# Power_supply.net
KiCad netlist of a schematic drawn in Altium Designer
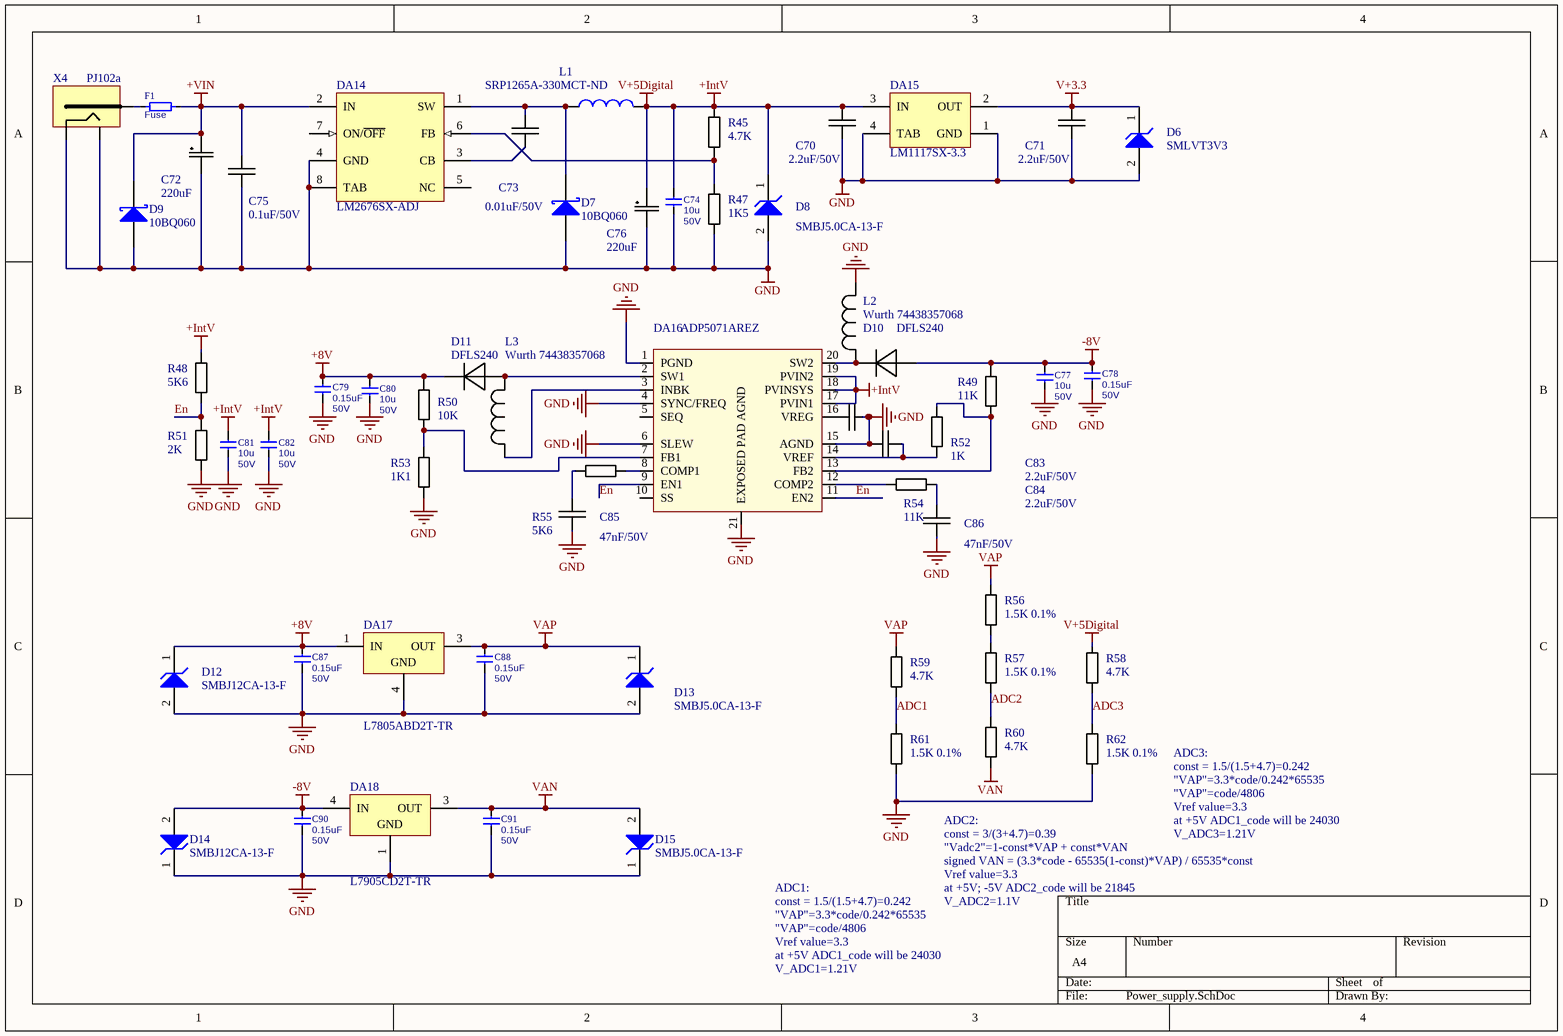
[diagram p0: Power_supply.SchDoc]

(export (version "E")
  (design (tool "Eeschema 10.0.6"))
  (components
    (comp (ref "C70")
      (value "2.2uF/50V")
      (footprint "CAPACITOR 0603")
      (fields (field (name "MANUFACTURER_PART_NUMBER") "C1608X7R1A225K080AC"))
      (libsource (lib "Maks_lib") (part "Capasitor"))
    )
    (comp (ref "C71")
      (value "2.2uF/50V")
      (footprint "CAPACITOR 0603")
      (fields (field (name "MANUFACTURER_PART_NUMBER") "C1608X7R1A225K080AC"))
      (libsource (lib "Maks_lib") (part "Capasitor"))
    )
    (comp (ref "C72")
      (value "220uF")
      (footprint "CapacitorG")
      (description "Конденсатор электролит бочонок 5мм, диаметр 13")
      (fields (field (name "MANUFACTURER_PART_NUMBER") "UWT1V221MNL1GS"))
      (libsource (lib "el") (part "CapPolBarrel"))
    )
    (comp (ref "C73")
      (value "0.01uF/50V")
      (footprint "CAPACITOR 0603")
      (fields (field (name "MANUFACTURER_PART_NUMBER") "CGA3E2X7R1H103K080AA"))
      (libsource (lib "Maks_lib") (part "Capasitor"))
    )
    (comp (ref "C74")
      (value "~")
      (footprint "Passive_components:C_1210")
      (description "Capacitor")
      (fields
        (field (name "CAPACITANCE") "10u")
        (field (name "VOLTAGE") "50V")
        (field (name "MANUFACTURER_PART_NUMBER") "CGA6P3X7S1H106M250AB")
      )
      (libsource (lib "Passive_components") (part "C_SMD_ceramic"))
    )
    (comp (ref "C75")
      (value "0.1uF/50V")
      (footprint "CAPACITOR 0603")
      (fields (field (name "MANUFACTURER_PART_NUMBER") "CGA3E2X7R1H104K080AA"))
      (libsource (lib "Maks_lib") (part "Capasitor"))
    )
    (comp (ref "C76")
      (value "220uF")
      (footprint "CapacitorG")
      (description "Конденсатор электролит бочонок 5мм, диаметр 13")
      (fields (field (name "MANUFACTURER_PART_NUMBER") "UWT1V221MNL1GS"))
      (libsource (lib "el") (part "CapPolBarrel"))
    )
    (comp (ref "C77")
      (value "~")
      (footprint "Passive_components:C_1210")
      (description "Capacitor")
      (fields
        (field (name "CAPACITANCE") "10u")
        (field (name "VOLTAGE") "50V")
        (field (name "MANUFACTURER_PART_NUMBER") "CGA6P3X7S1H106M250AB")
      )
      (libsource (lib "Passive_components") (part "C_SMD_ceramic"))
    )
    (comp (ref "C78")
      (value "~")
      (footprint "Passive_components:C_1206")
      (description "Capacitor")
      (fields
        (field (name "CAPACITANCE") "0.15uF")
        (field (name "VOLTAGE") "50V")
        (field (name "MANUFACTURER_PART_NUMBER") "ECP-U1C154MA5")
      )
      (libsource (lib "Passive_components") (part "C_SMD_ceramic"))
    )
    (comp (ref "C79")
      (value "~")
      (footprint "Passive_components:C_1206")
      (description "Capacitor")
      (fields
        (field (name "CAPACITANCE") "0.15uF")
        (field (name "VOLTAGE") "50V")
        (field (name "MANUFACTURER_PART_NUMBER") "ECP-U1C154MA5")
      )
      (libsource (lib "Passive_components") (part "C_SMD_ceramic"))
    )
    (comp (ref "C80")
      (value "~")
      (footprint "Passive_components:C_1210")
      (description "Capacitor")
      (fields
        (field (name "CAPACITANCE") "10u")
        (field (name "VOLTAGE") "50V")
        (field (name "MANUFACTURER_PART_NUMBER") "CGA6P3X7S1H106M250AB")
      )
      (libsource (lib "Passive_components") (part "C_SMD_ceramic"))
    )
    (comp (ref "C81")
      (value "~")
      (footprint "Passive_components:C_1210")
      (description "Capacitor")
      (fields
        (field (name "CAPACITANCE") "10u")
        (field (name "VOLTAGE") "50V")
        (field (name "MANUFACTURER_PART_NUMBER") "CGA6P3X7S1H106M250AB")
      )
      (libsource (lib "Passive_components") (part "C_SMD_ceramic"))
    )
    (comp (ref "C82")
      (value "~")
      (footprint "Passive_components:C_1210")
      (description "Capacitor")
      (fields
        (field (name "CAPACITANCE") "10u")
        (field (name "VOLTAGE") "50V")
        (field (name "MANUFACTURER_PART_NUMBER") "CGA6P3X7S1H106M250AB")
      )
      (libsource (lib "Passive_components") (part "C_SMD_ceramic"))
    )
    (comp (ref "C83")
      (value "2.2uF/50V")
      (footprint "CAPACITOR 0603")
      (fields (field (name "MANUFACTURER_PART_NUMBER") "C1608X7R1A225K080AC"))
      (libsource (lib "Maks_lib") (part "Capasitor"))
    )
    (comp (ref "C84")
      (value "2.2uF/50V")
      (footprint "CAPACITOR 0603")
      (fields (field (name "MANUFACTURER_PART_NUMBER") "C1608X7R1A225K080AC"))
      (libsource (lib "Maks_lib") (part "Capasitor"))
    )
    (comp (ref "C85")
      (value "47nF/50V")
      (footprint "CAPACITOR 0603")
      (fields (field (name "MANUFACTURER_PART_NUMBER") "C1608X8R1H473K080AA"))
      (libsource (lib "Maks_lib") (part "Capasitor"))
    )
    (comp (ref "C86")
      (value "47nF/50V")
      (footprint "CAPACITOR 0603")
      (fields (field (name "MANUFACTURER_PART_NUMBER") "C1608X8R1H473K080AA"))
      (libsource (lib "Maks_lib") (part "Capasitor"))
    )
    (comp (ref "C87")
      (value "~")
      (footprint "Passive_components:C_1206")
      (description "Capacitor")
      (fields
        (field (name "CAPACITANCE") "0.15uF")
        (field (name "VOLTAGE") "50V")
        (field (name "MANUFACTURER_PART_NUMBER") "ECP-U1C154MA5")
      )
      (libsource (lib "Passive_components") (part "C_SMD_ceramic"))
    )
    (comp (ref "C88")
      (value "~")
      (footprint "Passive_components:C_1206")
      (description "Capacitor")
      (fields
        (field (name "CAPACITANCE") "0.15uF")
        (field (name "VOLTAGE") "50V")
        (field (name "MANUFACTURER_PART_NUMBER") "ECP-U1C154MA5")
      )
      (libsource (lib "Passive_components") (part "C_SMD_ceramic"))
    )
    (comp (ref "C90")
      (value "~")
      (footprint "Passive_components:C_1206")
      (description "Capacitor")
      (fields
        (field (name "CAPACITANCE") "0.15uF")
        (field (name "VOLTAGE") "50V")
        (field (name "MANUFACTURER_PART_NUMBER") "ECP-U1C154MA5")
      )
      (libsource (lib "Passive_components") (part "C_SMD_ceramic"))
    )
    (comp (ref "C91")
      (value "~")
      (footprint "Passive_components:C_1206")
      (description "Capacitor")
      (fields
        (field (name "CAPACITANCE") "0.15uF")
        (field (name "VOLTAGE") "50V")
        (field (name "MANUFACTURER_PART_NUMBER") "ECP-U1C154MA5")
      )
      (libsource (lib "Passive_components") (part "C_SMD_ceramic"))
    )
    (comp (ref "D6")
      (value "SMLVT3V3")
      (footprint "ONSC-SMB-2-403A-03_H_V")
      (description "600 W Peak Power Zener Transient Voltage Suppressor, Unidirectional, 2-Pin SMB, Tape and Reel")
      (fields (field (name "MANUFACTURER") "On Semiconductor") (field (name "PARTNUMBER") "1SMB5.0AT3"))
      (libsource (lib "ON Semi Transient Voltage Suppressors (TVS)") (part "1SMB5.0AT3"))
    )
    (comp (ref "D7")
      (value "10BQ060")
      (footprint "SMB")
      (description "Schottky Rectifier")
      (fields
        (field (name "MANUFACTURER_PART_NUMBER") "10BQ060TR")
        (field (name "PUBLISHER") "Altium Limited")
      )
      (libsource (lib "IR Rectifier - Schottky") (part "10BQ060"))
    )
    (comp (ref "D8")
      (value "SMBJ5.0CA-13-F")
      (footprint "ONSC-SMB-2-403A-03_H_V")
      (description "600 W Peak Power Zener Transient Voltage Suppressor, Unidirectional, 2-Pin SMB, Tape and Reel")
      (fields (field (name "MANUFACTURER") "On Semiconductor") (field (name "PARTNUMBER") "1SMB5.0AT3"))
      (libsource (lib "ON Semi Transient Voltage Suppressors (TVS)") (part "1SMB5.0AT3"))
    )
    (comp (ref "D9")
      (value "10BQ060")
      (footprint "SMB")
      (description "Schottky Rectifier")
      (fields
        (field (name "MANUFACTURER_PART_NUMBER") "10BQ060TR")
        (field (name "PUBLISHER") "Altium Limited")
      )
      (libsource (lib "IR Rectifier - Schottky") (part "10BQ060"))
    )
    (comp (ref "D10")
      (value "DFLS240")
      (footprint "PowerDI™ 123")
      (fields (field (name "MANUFACTURER_PART_NUMBER") "DFLS240L-7"))
      (libsource (lib "Roman_lib") (part "DFLS240"))
    )
    (comp (ref "D11")
      (value "DFLS240")
      (footprint "PowerDI™ 123")
      (fields (field (name "MANUFACTURER_PART_NUMBER") "DFLS240L-7"))
      (libsource (lib "Roman_lib") (part "DFLS240"))
    )
    (comp (ref "D12")
      (value "SMBJ12CA-13-F")
      (footprint "ONSC-SMB-2-403A-03_H_V")
      (description "600 W Peak Power Zener Transient Voltage Suppressor, Unidirectional, 2-Pin SMB, Tape and Reel")
      (fields (field (name "MANUFACTURER") "On Semiconductor") (field (name "PARTNUMBER") "1SMB5.0AT3"))
      (libsource (lib "ON Semi Transient Voltage Suppressors (TVS)") (part "1SMB5.0AT3"))
    )
    (comp (ref "D13")
      (value "SMBJ5.0CA-13-F")
      (footprint "ONSC-SMB-2-403A-03_H_V")
      (description "600 W Peak Power Zener Transient Voltage Suppressor, Unidirectional, 2-Pin SMB, Tape and Reel")
      (fields (field (name "MANUFACTURER") "On Semiconductor") (field (name "PARTNUMBER") "1SMB5.0AT3"))
      (libsource (lib "ON Semi Transient Voltage Suppressors (TVS)") (part "1SMB5.0AT3"))
    )
    (comp (ref "D14")
      (value "SMBJ12CA-13-F")
      (footprint "ONSC-SMB-2-403A-03_H_V")
      (description "600 W Peak Power Zener Transient Voltage Suppressor, Unidirectional, 2-Pin SMB, Tape and Reel")
      (fields (field (name "MANUFACTURER") "On Semiconductor") (field (name "PARTNUMBER") "1SMB5.0AT3"))
      (libsource (lib "ON Semi Transient Voltage Suppressors (TVS)") (part "1SMB5.0AT3"))
    )
    (comp (ref "D15")
      (value "SMBJ5.0CA-13-F")
      (footprint "ONSC-SMB-2-403A-03_H_V")
      (description "600 W Peak Power Zener Transient Voltage Suppressor, Unidirectional, 2-Pin SMB, Tape and Reel")
      (fields (field (name "MANUFACTURER") "On Semiconductor") (field (name "PARTNUMBER") "1SMB5.0AT3"))
      (libsource (lib "ON Semi Transient Voltage Suppressors (TVS)") (part "1SMB5.0AT3"))
    )
    (comp (ref "DA14")
      (value "LM2676SX-ADJ")
      (footprint "TS7B_M")
      (description "SIMPLE SWITCHER® High Efficiency 3A Step-Down Voltage Regulator, 7-pin TO-263")
      (fields
        (field (name "PARTNUMBER") "LM2676S-3.3")
        (field (name "MANUFACTURER") "National Semiconductor")
      )
      (libsource (lib "National Semiconductor Switcher") (part "LM2676S-3.3"))
    )
    (comp (ref "DA15")
      (value "LM1117SX-3.3")
      (footprint "TS3B_N")
      (description "800mA Low-Dropout Linear Regulator, 3-pin TO-263")
      (fields
        (field (name "MANUFACTURER") "National Semiconductor")
        (field (name "MANUFACTURER_PART_NUMBER") "LM1117SX-3.3/NOPB")
      )
      (libsource (lib "National Semiconductor LDO") (part "LM1117SX-3.3"))
    )
    (comp (ref "DA16")
      (value "ADP5071AREZ")
      (footprint "20-TSSOP_exposed_pad")
      (libsource (lib "Roman_lib") (part "ADP5071"))
    )
    (comp (ref "DA17")
      (value "L7805ABD2T-TR")
      (footprint "TO-263_M")
      (description "Positive Voltage Regulator, 3-Pin D2PAK, Tape and Reel")
      (libsource (lib "STMicroelectronics Power Management Linear Regulator") (part "L7805ABD2T-TR"))
    )
    (comp (ref "DA18")
      (value "L7905CD2T-TR")
      (footprint "TO-263_M")
      (description "Negative Voltage Regulator, -5V, 3-Pin D2PAK, Tape and Reel")
      (libsource (lib "STMicroelectronics Power Management Linear Regulator") (part "L7905CD2T-TR"))
    )
    (comp (ref "F1")
      (value "Fuse")
      (footprint "R_1206")
      (description "Resistor")
      (fields (field (name "MANUFACTURER_PART_NUMBER") "NANOSMDH075F-02"))
      (libsource (lib "01_Sch_lib") (part "R1206"))
    )
    (comp (ref "L1")
      (value "SRP1265A-330MCT-ND")
      (footprint "Inductor_RLF12545")
      (libsource (lib "Roman_lib") (part "Inductor_RLF12545"))
    )
    (comp (ref "L2")
      (value "Wurth 74438357068")
      (footprint "Wurth74438357068")
      (libsource (lib "Roman_lib") (part "L"))
    )
    (comp (ref "L3")
      (value "Wurth 74438357068")
      (footprint "Wurth74438357068")
      (libsource (lib "Roman_lib") (part "L"))
    )
    (comp (ref "R45")
      (value "4.7K")
      (footprint "Resistor 0603")
      (fields (field (name "MANUFACTURER_PART_NUMBER") "ERJ-3EKF4701V"))
      (libsource (lib "Maks_lib") (part "Resistor"))
    )
    (comp (ref "R47")
      (value "1K5")
      (footprint "Resistor 0603")
      (fields (field (name "MANUFACTURER_PART_NUMBER") "ERJ-PB3B1501V"))
      (libsource (lib "Maks_lib") (part "Resistor"))
    )
    (comp (ref "R48")
      (value "5K6")
      (footprint "Resistor 0603")
      (fields (field (name "MANUFACTURER_PART_NUMBER") "ERJ-3EKF5601V"))
      (libsource (lib "Maks_lib") (part "Resistor"))
    )
    (comp (ref "R49")
      (value "11K")
      (footprint "Resistor 0603")
      (fields (field (name "MANUFACTURER_PART_NUMBER") "ERJ-3EKF1102V"))
      (libsource (lib "Maks_lib") (part "Resistor"))
    )
    (comp (ref "R50")
      (value "10K")
      (footprint "Resistor 0603")
      (fields (field (name "MANUFACTURER_PART_NUMBER") "ERJ-3EKF1002V"))
      (libsource (lib "Maks_lib") (part "Resistor"))
    )
    (comp (ref "R51")
      (value "2K")
      (footprint "Resistor 0603")
      (fields (field (name "MANUFACTURER_PART_NUMBER") "ERJ-3EKF2001V"))
      (libsource (lib "Maks_lib") (part "Resistor"))
    )
    (comp (ref "R52")
      (value "1K")
      (footprint "Resistor 0603")
      (fields (field (name "MANUFACTURER_PART_NUMBER") "ERJ-3EKF1001V"))
      (libsource (lib "Maks_lib") (part "Resistor"))
    )
    (comp (ref "R53")
      (value "1K1")
      (footprint "Resistor 0603")
      (fields (field (name "MANUFACTURER_PART_NUMBER") "ERJ-3EKF1101V"))
      (libsource (lib "Maks_lib") (part "Resistor"))
    )
    (comp (ref "R54")
      (value "11K")
      (footprint "Resistor 0603")
      (fields (field (name "MANUFACTURER_PART_NUMBER") "ERJ-3EKF1102V"))
      (libsource (lib "Maks_lib") (part "Resistor"))
    )
    (comp (ref "R55")
      (value "5K6")
      (footprint "Resistor 0603")
      (fields (field (name "MANUFACTURER_PART_NUMBER") "ERJ-3EKF5601V"))
      (libsource (lib "Maks_lib") (part "Resistor"))
    )
    (comp (ref "R56")
      (value "1.5K 0.1%")
      (footprint "Resistor 0603")
      (fields (field (name "MANUFACTURER_PART_NUMBER") "ERJ-PB3B1501V"))
      (libsource (lib "Maks_lib") (part "Resistor"))
    )
    (comp (ref "R57")
      (value "1.5K 0.1%")
      (footprint "Resistor 0603")
      (fields (field (name "MANUFACTURER_PART_NUMBER") "ERJ-PB3B1501V"))
      (libsource (lib "Maks_lib") (part "Resistor"))
    )
    (comp (ref "R58")
      (value "4.7K")
      (footprint "Resistor 0603")
      (fields (field (name "MANUFACTURER_PART_NUMBER") "ERJ-3EKF4701V"))
      (libsource (lib "Maks_lib") (part "Resistor"))
    )
    (comp (ref "R59")
      (value "4.7K")
      (footprint "Resistor 0603")
      (fields (field (name "MANUFACTURER_PART_NUMBER") "ERJ-3EKF4701V"))
      (libsource (lib "Maks_lib") (part "Resistor"))
    )
    (comp (ref "R60")
      (value "4.7K")
      (footprint "Resistor 0603")
      (fields (field (name "MANUFACTURER_PART_NUMBER") "ERJ-3EKF4701V"))
      (libsource (lib "Maks_lib") (part "Resistor"))
    )
    (comp (ref "R61")
      (value "1.5K 0.1%")
      (footprint "Resistor 0603")
      (fields (field (name "MANUFACTURER_PART_NUMBER") "ERJ-PB3B1501V"))
      (libsource (lib "Maks_lib") (part "Resistor"))
    )
    (comp (ref "R62")
      (value "1.5K 0.1%")
      (footprint "Resistor 0603")
      (fields (field (name "MANUFACTURER_PART_NUMBER") "ERJ-PB3B1501V"))
      (libsource (lib "Maks_lib") (part "Resistor"))
    )
    (comp (ref "X4")
      (value "PJ102a")
      (footprint "Conn_pj-102a")
      (description "PJ-102A barrel jack 2.1x5.5x9.0mm")
      (libsource (lib "Connectors_Vas") (part "PJ102a"))
    )
  )
  (nets
    (net (code "1") (name "+8V") (class "Default")
      (node (ref "C79") (pin "1") (pintype "passive"))
      (node (ref "C80") (pin "2") (pintype "passive"))
      (node (ref "C87") (pin "1") (pintype "passive"))
      (node (ref "D11") (pin "2") (pinfunction "2_2") (pintype "passive"))
      (node (ref "D12") (pin "1") (pinfunction "K_1") (pintype "passive"))
      (node (ref "DA17") (pin "1") (pinfunction "IN_1") (pintype "power_in"))
      (node (ref "R50") (pin "2") (pinfunction "2_2") (pintype "passive"))
    )
    (net (code "2") (name "+IntV") (class "Default")
      (node (ref "C70") (pin "2") (pinfunction "2_2") (pintype "passive"))
      (node (ref "C74") (pin "2") (pintype "passive"))
      (node (ref "C76") (pin "2") (pinfunction "2_2") (pintype "passive"))
      (node (ref "C81") (pin "2") (pintype "passive"))
      (node (ref "C82") (pin "2") (pintype "passive"))
      (node (ref "D8") (pin "1") (pinfunction "K_1") (pintype "passive"))
      (node (ref "DA15") (pin "3") (pinfunction "IN_3") (pintype "power_in"))
      (node (ref "DA16") (pin "17") (pinfunction "PVIN1_17") (pintype "passive"))
      (node (ref "DA16") (pin "18") (pinfunction "PVINSYS_18") (pintype "passive"))
      (node (ref "DA16") (pin "19") (pinfunction "PVIN2_19") (pintype "passive"))
      (node (ref "L1") (pin "2") (pinfunction "2_2") (pintype "passive"))
      (node (ref "R45") (pin "2") (pinfunction "2_2") (pintype "passive"))
      (node (ref "R48") (pin "2") (pinfunction "2_2") (pintype "passive"))
      (node (ref "R58") (pin "2") (pinfunction "2_2") (pintype "passive"))
    )
    (net (code "3") (name "+VIN") (class "Default")
      (node (ref "C72") (pin "2") (pinfunction "2_2") (pintype "passive"))
      (node (ref "C75") (pin "2") (pinfunction "2_2") (pintype "passive"))
      (node (ref "D9") (pin "2") (pinfunction "K_2") (pintype "passive"))
      (node (ref "DA14") (pin "2") (pinfunction "IN_2") (pintype "power_in"))
      (node (ref "F1") (pin "2") (pintype "passive"))
    )
    (net (code "4") (name "-8V") (class "Default")
      (node (ref "C77") (pin "2") (pintype "passive"))
      (node (ref "C78") (pin "1") (pintype "passive"))
      (node (ref "C90") (pin "1") (pintype "passive"))
      (node (ref "D10") (pin "1") (pinfunction "1_1") (pintype "passive"))
      (node (ref "D14") (pin "2") (pinfunction "A_2") (pintype "passive"))
      (node (ref "DA18") (pin "4") (pinfunction "IN_4") (pintype "power_in"))
      (node (ref "R49") (pin "2") (pinfunction "2_2") (pintype "passive"))
    )
    (net (code "5") (name "/ADC1") (class "Default")
      (node (ref "R59") (pin "1") (pinfunction "1_1") (pintype "passive"))
      (node (ref "R61") (pin "2") (pinfunction "2_2") (pintype "passive"))
    )
    (net (code "6") (name "/ADC2") (class "Default")
      (node (ref "R57") (pin "1") (pinfunction "1_1") (pintype "passive"))
      (node (ref "R60") (pin "2") (pinfunction "2_2") (pintype "passive"))
    )
    (net (code "7") (name "/ADC3") (class "Default")
      (node (ref "R58") (pin "1") (pinfunction "1_1") (pintype "passive"))
      (node (ref "R62") (pin "2") (pinfunction "2_2") (pintype "passive"))
    )
    (net (code "8") (name "/En") (class "Default")
      (node (ref "DA16") (pin "11") (pinfunction "EN2_11") (pintype "passive"))
      (node (ref "DA16") (pin "9") (pinfunction "EN1_9") (pintype "passive"))
      (node (ref "R48") (pin "1") (pinfunction "1_1") (pintype "passive"))
      (node (ref "R51") (pin "2") (pinfunction "2_2") (pintype "passive"))
    )
    (net (code "9") (name "GND") (class "Default")
      (node (ref "C70") (pin "1") (pinfunction "1_1") (pintype "passive"))
      (node (ref "C71") (pin "1") (pinfunction "1_1") (pintype "passive"))
      (node (ref "C72") (pin "1") (pinfunction "1_1") (pintype "passive"))
      (node (ref "C74") (pin "1") (pintype "passive"))
      (node (ref "C75") (pin "1") (pinfunction "1_1") (pintype "passive"))
      (node (ref "C76") (pin "1") (pinfunction "1_1") (pintype "passive"))
      (node (ref "C77") (pin "1") (pintype "passive"))
      (node (ref "C78") (pin "2") (pintype "passive"))
      (node (ref "C79") (pin "2") (pintype "passive"))
      (node (ref "C80") (pin "1") (pintype "passive"))
      (node (ref "C81") (pin "1") (pintype "passive"))
      (node (ref "C82") (pin "1") (pintype "passive"))
      (node (ref "C83") (pin "1") (pinfunction "1_1") (pintype "passive"))
      (node (ref "C84") (pin "2") (pinfunction "2_2") (pintype "passive"))
      (node (ref "C85") (pin "1") (pinfunction "1_1") (pintype "passive"))
      (node (ref "C86") (pin "1") (pinfunction "1_1") (pintype "passive"))
      (node (ref "C87") (pin "2") (pintype "passive"))
      (node (ref "C88") (pin "2") (pintype "passive"))
      (node (ref "C90") (pin "2") (pintype "passive"))
      (node (ref "C91") (pin "2") (pintype "passive"))
      (node (ref "D12") (pin "2") (pinfunction "A_2") (pintype "passive"))
      (node (ref "D13") (pin "2") (pinfunction "A_2") (pintype "passive"))
      (node (ref "D14") (pin "1") (pinfunction "K_1") (pintype "passive"))
      (node (ref "D15") (pin "1") (pinfunction "K_1") (pintype "passive"))
      (node (ref "D6") (pin "2") (pinfunction "A_2") (pintype "passive"))
      (node (ref "D7") (pin "1") (pinfunction "A_1") (pintype "passive"))
      (node (ref "D8") (pin "2") (pinfunction "A_2") (pintype "passive"))
      (node (ref "D9") (pin "1") (pinfunction "A_1") (pintype "passive"))
      (node (ref "DA14") (pin "4") (pinfunction "GND_4") (pintype "power_in"))
      (node (ref "DA14") (pin "8") (pinfunction "TAB_8") (pintype "power_in"))
      (node (ref "DA15") (pin "1") (pinfunction "GND_1") (pintype "power_in"))
      (node (ref "DA15") (pin "4") (pinfunction "TAB_4") (pintype "power_in"))
      (node (ref "DA16") (pin "1") (pinfunction "PGND_1") (pintype "passive"))
      (node (ref "DA16") (pin "15") (pinfunction "AGND_15") (pintype "passive"))
      (node (ref "DA16") (pin "21") (pinfunction "EXPOSED_PAD_AGND_21") (pintype "passive"))
      (node (ref "DA16") (pin "4") (pinfunction "SYNC/FREQ_4") (pintype "passive"))
      (node (ref "DA16") (pin "6") (pinfunction "SLEW_6") (pintype "passive"))
      (node (ref "DA17") (pin "4") (pinfunction "GND_4") (pintype "power_in"))
      (node (ref "DA18") (pin "1") (pinfunction "GND_1") (pintype "power_in"))
      (node (ref "L2") (pin "1") (pinfunction "1_1") (pintype "passive"))
      (node (ref "R47") (pin "1") (pinfunction "1_1") (pintype "passive"))
      (node (ref "R51") (pin "1") (pinfunction "1_1") (pintype "passive"))
      (node (ref "R53") (pin "1") (pinfunction "1_1") (pintype "passive"))
      (node (ref "R61") (pin "1") (pinfunction "1_1") (pintype "passive"))
      (node (ref "R62") (pin "1") (pinfunction "1_1") (pintype "passive"))
      (node (ref "X4") (pin "2") (pinfunction "2_2") (pintype "passive"))
      (node (ref "X4") (pin "3") (pinfunction "3_3") (pintype "passive"))
    )
    (net (code "10") (name "Net-(C85-Pad2)") (class "Default")
      (node (ref "C85") (pin "2") (pinfunction "2_2") (pintype "passive"))
      (node (ref "R55") (pin "2") (pinfunction "2_2") (pintype "passive"))
    )
    (net (code "11") (name "Net-(C86-Pad2)") (class "Default")
      (node (ref "C86") (pin "2") (pinfunction "2_2") (pintype "passive"))
      (node (ref "R54") (pin "1") (pinfunction "1_1") (pintype "passive"))
    )
    (net (code "12") (name "Net-(D7-K)") (class "Default")
      (node (ref "C73") (pin "2") (pinfunction "2_2") (pintype "passive"))
      (node (ref "D7") (pin "2") (pinfunction "K_2") (pintype "passive"))
      (node (ref "DA14") (pin "1") (pinfunction "SW_1") (pintype "power_in"))
      (node (ref "L1") (pin "1") (pinfunction "1_1") (pintype "passive"))
    )
    (net (code "13") (name "Net-(DA14-CB)") (class "Default")
      (node (ref "C73") (pin "1") (pinfunction "1_1") (pintype "passive"))
      (node (ref "DA14") (pin "3") (pinfunction "CB_3") (pintype "passive"))
    )
    (net (code "14") (name "Net-(DA14-FB)") (class "Default")
      (node (ref "DA14") (pin "6") (pinfunction "FB_6") (pintype "input"))
      (node (ref "R45") (pin "1") (pinfunction "1_1") (pintype "passive"))
      (node (ref "R47") (pin "2") (pinfunction "2_2") (pintype "passive"))
    )
    (net (code "15") (name "Net-(DA16-COMP1)") (class "Default")
      (node (ref "DA16") (pin "8") (pinfunction "COMP1_8") (pintype "passive"))
      (node (ref "R55") (pin "1") (pinfunction "1_1") (pintype "passive"))
    )
    (net (code "16") (name "Net-(DA16-COMP2)") (class "Default")
      (node (ref "DA16") (pin "12") (pinfunction "COMP2_12") (pintype "passive"))
      (node (ref "R54") (pin "2") (pinfunction "2_2") (pintype "passive"))
    )
    (net (code "17") (name "Net-(DA16-FB1)") (class "Default")
      (node (ref "DA16") (pin "7") (pinfunction "FB1_7") (pintype "passive"))
      (node (ref "R50") (pin "1") (pinfunction "1_1") (pintype "passive"))
      (node (ref "R53") (pin "2") (pinfunction "2_2") (pintype "passive"))
    )
    (net (code "18") (name "Net-(DA16-FB2)") (class "Default")
      (node (ref "DA16") (pin "13") (pinfunction "FB2_13") (pintype "passive"))
      (node (ref "R49") (pin "1") (pinfunction "1_1") (pintype "passive"))
      (node (ref "R52") (pin "2") (pinfunction "2_2") (pintype "passive"))
    )
    (net (code "19") (name "Net-(DA16-INBK)") (class "Default")
      (node (ref "DA16") (pin "3") (pinfunction "INBK_3") (pintype "passive"))
      (node (ref "L3") (pin "2") (pinfunction "2_2") (pintype "passive"))
    )
    (net (code "20") (name "Net-(DA16-SW1)") (class "Default")
      (node (ref "D11") (pin "1") (pinfunction "1_1") (pintype "passive"))
      (node (ref "DA16") (pin "2") (pinfunction "SW1_2") (pintype "passive"))
      (node (ref "L3") (pin "1") (pinfunction "1_1") (pintype "passive"))
    )
    (net (code "21") (name "Net-(DA16-SW2)") (class "Default")
      (node (ref "D10") (pin "2") (pinfunction "2_2") (pintype "passive"))
      (node (ref "DA16") (pin "20") (pinfunction "SW2_20") (pintype "passive"))
      (node (ref "L2") (pin "2") (pinfunction "2_2") (pintype "passive"))
    )
    (net (code "22") (name "Net-(DA16-VREF)") (class "Default")
      (node (ref "C84") (pin "1") (pinfunction "1_1") (pintype "passive"))
      (node (ref "DA16") (pin "14") (pinfunction "VREF_14") (pintype "passive"))
      (node (ref "R52") (pin "1") (pinfunction "1_1") (pintype "passive"))
    )
    (net (code "23") (name "Net-(DA16-VREG)") (class "Default")
      (node (ref "C83") (pin "2") (pinfunction "2_2") (pintype "passive"))
      (node (ref "DA16") (pin "16") (pinfunction "VREG_16") (pintype "passive"))
    )
    (net (code "24") (name "Net-(F1-Pad1)") (class "Default")
      (node (ref "F1") (pin "1") (pintype "passive"))
      (node (ref "X4") (pin "1") (pinfunction "1_1") (pintype "passive"))
    )
    (net (code "25") (name "Net-(R56-Pad1)") (class "Default")
      (node (ref "R56") (pin "1") (pinfunction "1_1") (pintype "passive"))
      (node (ref "R57") (pin "2") (pinfunction "2_2") (pintype "passive"))
    )
    (net (code "26") (name "V+3.3") (class "Default")
      (node (ref "C71") (pin "2") (pinfunction "2_2") (pintype "passive"))
      (node (ref "D6") (pin "1") (pinfunction "K_1") (pintype "passive"))
      (node (ref "DA15") (pin "2") (pinfunction "OUT_2") (pintype "power_in"))
    )
    (net (code "27") (name "VAN") (class "Default")
      (node (ref "C91") (pin "1") (pintype "passive"))
      (node (ref "D15") (pin "2") (pinfunction "A_2") (pintype "passive"))
      (node (ref "DA18") (pin "3") (pinfunction "OUT_3") (pintype "power_in"))
      (node (ref "R60") (pin "1") (pinfunction "1_1") (pintype "passive"))
    )
    (net (code "28") (name "VAP") (class "Default")
      (node (ref "C88") (pin "1") (pintype "passive"))
      (node (ref "D13") (pin "1") (pinfunction "K_1") (pintype "passive"))
      (node (ref "DA17") (pin "3") (pinfunction "OUT_3") (pintype "power_in"))
      (node (ref "R56") (pin "2") (pinfunction "2_2") (pintype "passive"))
      (node (ref "R59") (pin "2") (pinfunction "2_2") (pintype "passive"))
    )
    (net (code "29") (name "unconnected-(DA14-NC-Pad5)") (class "Default")
      (node (ref "DA14") (pin "5") (pinfunction "NC_5") (pintype "passive"))
    )
    (net (code "30") (name "unconnected-(DA14-ON{slash}~{OFF}-Pad7)") (class "Default")
      (node (ref "DA14") (pin "7") (pinfunction "ON/~{OFF}_7") (pintype "input"))
    )
    (net (code "31") (name "unconnected-(DA16-SEQ-Pad5)") (class "Default")
      (node (ref "DA16") (pin "5") (pinfunction "SEQ_5") (pintype "passive"))
    )
    (net (code "32") (name "unconnected-(DA16-SS-Pad10)") (class "Default")
      (node (ref "DA16") (pin "10") (pinfunction "SS_10") (pintype "passive"))
    )
  )
)
